# Benchtop_Power_Supply-v13.net
KiCad netlist of a schematic drawn in EAGLE
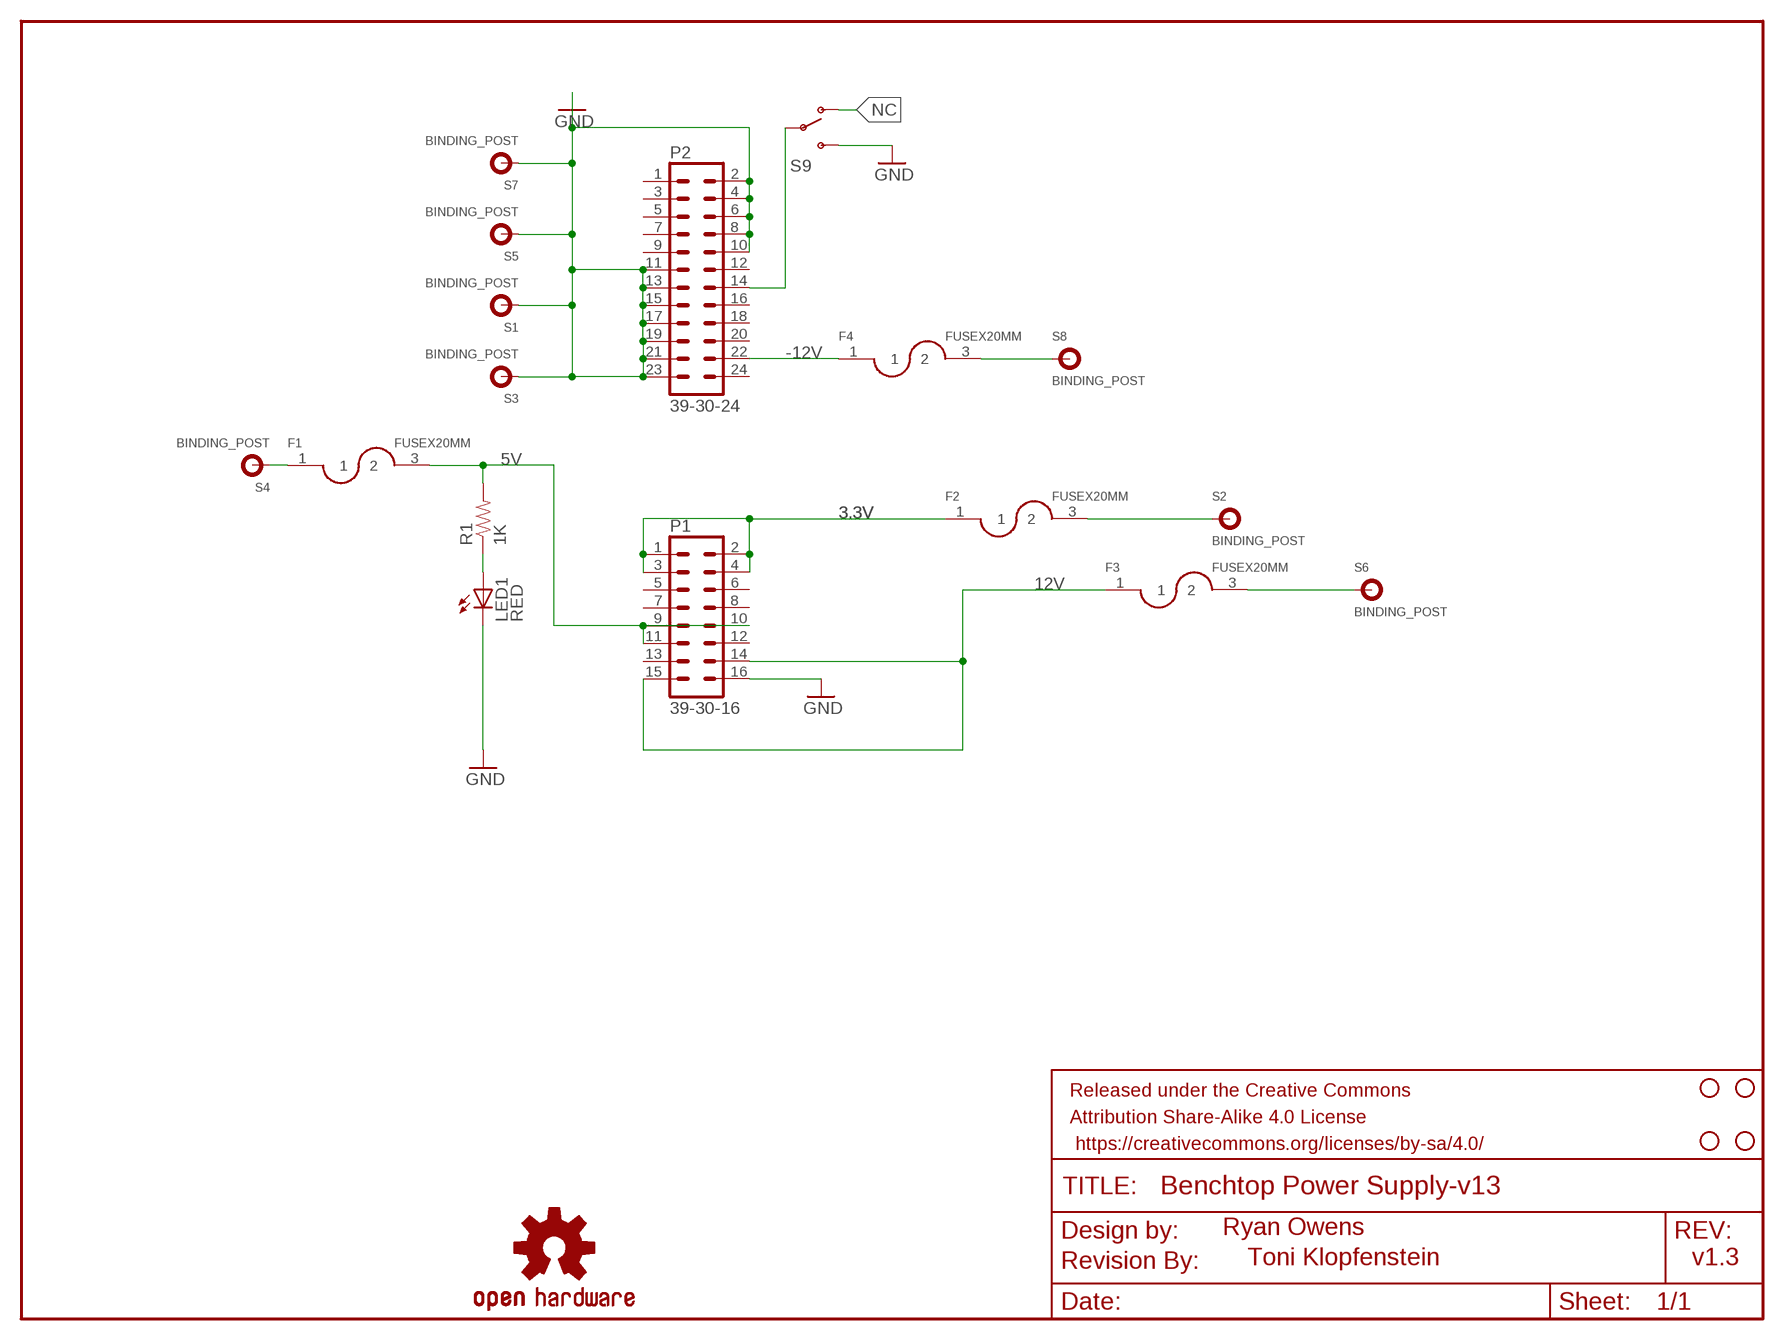
[diagram p0: schematic, sheet 1]

(export (version "E")
  (design (tool "Eeschema 10.0.6"))
  (components
    (comp (ref "F1")
      (value "FUSEX20MM")
      (footprint "eagle-import:FUSE_5MM")
      (libsource (lib "eagle-import") (part "FUSEX20MM"))
    )
    (comp (ref "F2")
      (value "FUSEX20MM")
      (footprint "eagle-import:FUSE_5MM")
      (libsource (lib "eagle-import") (part "FUSEX20MM"))
    )
    (comp (ref "F3")
      (value "FUSEX20MM")
      (footprint "eagle-import:FUSE_5MM")
      (libsource (lib "eagle-import") (part "FUSEX20MM"))
    )
    (comp (ref "F4")
      (value "FUSEX20MM")
      (footprint "eagle-import:FUSE_5MM")
      (libsource (lib "eagle-import") (part "FUSEX20MM"))
    )
    (comp (ref "FRAME1")
      (value "FRAME-LETTER")
      (footprint "eagle-import:CREATIVE_COMMONS")
      (libsource (lib "eagle-import") (part "FRAME-LETTER"))
    )
    (comp (ref "JP2")
      (value "STAND-OFF")
      (footprint "eagle-import:STAND-OFF")
      (libsource (lib "eagle-import") (part "STAND-OFF"))
    )
    (comp (ref "JP3")
      (value "STAND-OFF")
      (footprint "eagle-import:STAND-OFF")
      (libsource (lib "eagle-import") (part "STAND-OFF"))
    )
    (comp (ref "JP4")
      (value "STAND-OFF")
      (footprint "eagle-import:STAND-OFF")
      (libsource (lib "eagle-import") (part "STAND-OFF"))
    )
    (comp (ref "JP5")
      (value "STAND-OFF")
      (footprint "eagle-import:STAND-OFF")
      (libsource (lib "eagle-import") (part "STAND-OFF"))
    )
    (comp (ref "LED1")
      (value "RED")
      (footprint "eagle-import:LED5MM")
      (libsource (lib "eagle-import") (part "LED5MM"))
    )
    (comp (ref "LOGO1")
      (value "OSHW-LOGOL")
      (footprint "eagle-import:OSHW-LOGO-L")
      (libsource (lib "eagle-import") (part "OSHW-LOGOL"))
    )
    (comp (ref "P1")
      (value "39-30-16")
      (footprint "eagle-import:39-30-_16_")
      (libsource (lib "eagle-import") (part "39-30-?16?"))
    )
    (comp (ref "P2")
      (value "39-30-24")
      (footprint "eagle-import:39-30-_24_")
      (libsource (lib "eagle-import") (part "39-30-?24?"))
    )
    (comp (ref "R1")
      (value "1K")
      (footprint "eagle-import:AXIAL-0.3")
      (libsource (lib "eagle-import") (part "RESISTORPTH1"))
    )
    (comp (ref "S1")
      (value "BINDING_POST")
      (footprint "eagle-import:BINDING_POST")
      (libsource (lib "eagle-import") (part "BINDING_POST"))
    )
    (comp (ref "S2")
      (value "BINDING_POST")
      (footprint "eagle-import:BINDING_POST")
      (libsource (lib "eagle-import") (part "BINDING_POST"))
    )
    (comp (ref "S3")
      (value "BINDING_POST")
      (footprint "eagle-import:BINDING_POST")
      (libsource (lib "eagle-import") (part "BINDING_POST"))
    )
    (comp (ref "S4")
      (value "BINDING_POST")
      (footprint "eagle-import:BINDING_POST")
      (libsource (lib "eagle-import") (part "BINDING_POST"))
    )
    (comp (ref "S5")
      (value "BINDING_POST")
      (footprint "eagle-import:BINDING_POST")
      (libsource (lib "eagle-import") (part "BINDING_POST"))
    )
    (comp (ref "S6")
      (value "BINDING_POST")
      (footprint "eagle-import:BINDING_POST")
      (libsource (lib "eagle-import") (part "BINDING_POST"))
    )
    (comp (ref "S7")
      (value "BINDING_POST")
      (footprint "eagle-import:BINDING_POST")
      (libsource (lib "eagle-import") (part "BINDING_POST"))
    )
    (comp (ref "S8")
      (value "BINDING_POST")
      (footprint "eagle-import:BINDING_POST")
      (libsource (lib "eagle-import") (part "BINDING_POST"))
    )
    (comp (ref "S9")
      (value "SWITCH-SPDTKIT")
      (footprint "eagle-import:SWITCH-SPDT_KIT")
      (libsource (lib "eagle-import") (part "SWITCH-SPDTKIT"))
    )
    (comp (ref "U$1")
      (value "REVISION")
      (footprint "eagle-import:REVISION")
      (libsource (lib "eagle-import") (part "REVISION"))
    )
  )
  (nets
    (net (code "1") (name "/-12V") (class "Default")
      (node (ref "F4") (pin "1") (pinfunction "1_1") (pintype "bidirectional"))
      (node (ref "P2") (pin "22") (pinfunction "22_22") (pintype "passive"))
    )
    (net (code "2") (name "/3.3V") (class "Default")
      (node (ref "F2") (pin "1") (pinfunction "1_1") (pintype "bidirectional"))
      (node (ref "P1") (pin "1") (pinfunction "1_1") (pintype "passive"))
      (node (ref "P1") (pin "2") (pinfunction "2_2") (pintype "passive"))
      (node (ref "P1") (pin "3") (pinfunction "3_3") (pintype "passive"))
      (node (ref "P1") (pin "4") (pinfunction "4_4") (pintype "passive"))
    )
    (net (code "3") (name "/5V") (class "Default")
      (node (ref "F1") (pin "3") (pinfunction "2_3") (pintype "bidirectional"))
      (node (ref "P1") (pin "10") (pinfunction "10_10") (pintype "passive"))
      (node (ref "P1") (pin "11") (pinfunction "11_11") (pintype "passive"))
      (node (ref "P1") (pin "9") (pinfunction "9_9") (pintype "passive"))
      (node (ref "R1") (pin "P$2") (pinfunction "2_P$2") (pintype "passive"))
    )
    (net (code "4") (name "/12V") (class "Default")
      (node (ref "F3") (pin "1") (pinfunction "1_1") (pintype "bidirectional"))
      (node (ref "P1") (pin "14") (pinfunction "14_14") (pintype "passive"))
      (node (ref "P1") (pin "15") (pinfunction "15_15") (pintype "passive"))
    )
    (net (code "5") (name "GND") (class "Default")
      (node (ref "LED1") (pin "K") (pinfunction "C_K") (pintype "passive"))
      (node (ref "P1") (pin "16") (pinfunction "16_16") (pintype "passive"))
      (node (ref "P2") (pin "10") (pinfunction "10_10") (pintype "passive"))
      (node (ref "P2") (pin "11") (pinfunction "11_11") (pintype "passive"))
      (node (ref "P2") (pin "13") (pinfunction "13_13") (pintype "passive"))
      (node (ref "P2") (pin "15") (pinfunction "15_15") (pintype "passive"))
      (node (ref "P2") (pin "17") (pinfunction "17_17") (pintype "passive"))
      (node (ref "P2") (pin "19") (pinfunction "19_19") (pintype "passive"))
      (node (ref "P2") (pin "2") (pinfunction "2_2") (pintype "passive"))
      (node (ref "P2") (pin "21") (pinfunction "21_21") (pintype "passive"))
      (node (ref "P2") (pin "23") (pinfunction "23_23") (pintype "passive"))
      (node (ref "P2") (pin "4") (pinfunction "4_4") (pintype "passive"))
      (node (ref "P2") (pin "6") (pinfunction "6_6") (pintype "passive"))
      (node (ref "P2") (pin "8") (pinfunction "8_8") (pintype "passive"))
      (node (ref "S1") (pin "P$1") (pinfunction "P$1_P$1") (pintype "bidirectional"))
      (node (ref "S3") (pin "P$1") (pinfunction "P$1_P$1") (pintype "bidirectional"))
      (node (ref "S5") (pin "P$1") (pinfunction "P$1_P$1") (pintype "bidirectional"))
      (node (ref "S7") (pin "P$1") (pinfunction "P$1_P$1") (pintype "bidirectional"))
      (node (ref "S9") (pin "3") (pinfunction "S_3") (pintype "passive"))
    )
    (net (code "6") (name "NC") (class "Default")
      (node (ref "S9") (pin "1") (pinfunction "O_1") (pintype "passive"))
    )
    (net (code "7") (name "Net-(F1-Pad1)") (class "Default")
      (node (ref "F1") (pin "1") (pinfunction "1_1") (pintype "bidirectional"))
      (node (ref "S4") (pin "P$1") (pinfunction "P$1_P$1") (pintype "bidirectional"))
    )
    (net (code "8") (name "Net-(F2-2)") (class "Default")
      (node (ref "F2") (pin "3") (pinfunction "2_3") (pintype "bidirectional"))
      (node (ref "S2") (pin "P$1") (pinfunction "P$1_P$1") (pintype "bidirectional"))
    )
    (net (code "9") (name "Net-(F3-2)") (class "Default")
      (node (ref "F3") (pin "3") (pinfunction "2_3") (pintype "bidirectional"))
      (node (ref "S6") (pin "P$1") (pinfunction "P$1_P$1") (pintype "bidirectional"))
    )
    (net (code "10") (name "Net-(F4-2)") (class "Default")
      (node (ref "F4") (pin "3") (pinfunction "2_3") (pintype "bidirectional"))
      (node (ref "S8") (pin "P$1") (pinfunction "P$1_P$1") (pintype "bidirectional"))
    )
    (net (code "11") (name "Net-(R1-1)") (class "Default")
      (node (ref "LED1") (pin "A") (pinfunction "A_A") (pintype "passive"))
      (node (ref "R1") (pin "P$1") (pinfunction "1_P$1") (pintype "passive"))
    )
    (net (code "12") (name "Net-(S9-P)") (class "Default")
      (node (ref "P2") (pin "14") (pinfunction "14_14") (pintype "passive"))
      (node (ref "S9") (pin "2") (pinfunction "P_2") (pintype "passive"))
    )
    (net (code "13") (name "unconnected-(P1-Pad5)") (class "Default")
      (node (ref "P1") (pin "5") (pinfunction "5_5") (pintype "passive"))
    )
    (net (code "14") (name "unconnected-(P1-Pad6)") (class "Default")
      (node (ref "P1") (pin "6") (pinfunction "6_6") (pintype "passive"))
    )
    (net (code "15") (name "unconnected-(P1-Pad7)") (class "Default")
      (node (ref "P1") (pin "7") (pinfunction "7_7") (pintype "passive"))
    )
    (net (code "16") (name "unconnected-(P1-Pad8)") (class "Default")
      (node (ref "P1") (pin "8") (pinfunction "8_8") (pintype "passive"))
    )
    (net (code "17") (name "unconnected-(P1-Pad12)") (class "Default")
      (node (ref "P1") (pin "12") (pinfunction "12_12") (pintype "passive"))
    )
    (net (code "18") (name "unconnected-(P1-Pad13)") (class "Default")
      (node (ref "P1") (pin "13") (pinfunction "13_13") (pintype "passive"))
    )
    (net (code "19") (name "unconnected-(P2-Pad1)") (class "Default")
      (node (ref "P2") (pin "1") (pinfunction "1_1") (pintype "passive"))
    )
    (net (code "20") (name "unconnected-(P2-Pad3)") (class "Default")
      (node (ref "P2") (pin "3") (pinfunction "3_3") (pintype "passive"))
    )
    (net (code "21") (name "unconnected-(P2-Pad5)") (class "Default")
      (node (ref "P2") (pin "5") (pinfunction "5_5") (pintype "passive"))
    )
    (net (code "22") (name "unconnected-(P2-Pad7)") (class "Default")
      (node (ref "P2") (pin "7") (pinfunction "7_7") (pintype "passive"))
    )
    (net (code "23") (name "unconnected-(P2-Pad9)") (class "Default")
      (node (ref "P2") (pin "9") (pinfunction "9_9") (pintype "passive"))
    )
    (net (code "24") (name "unconnected-(P2-Pad12)") (class "Default")
      (node (ref "P2") (pin "12") (pinfunction "12_12") (pintype "passive"))
    )
    (net (code "25") (name "unconnected-(P2-Pad16)") (class "Default")
      (node (ref "P2") (pin "16") (pinfunction "16_16") (pintype "passive"))
    )
    (net (code "26") (name "unconnected-(P2-Pad18)") (class "Default")
      (node (ref "P2") (pin "18") (pinfunction "18_18") (pintype "passive"))
    )
    (net (code "27") (name "unconnected-(P2-Pad20)") (class "Default")
      (node (ref "P2") (pin "20") (pinfunction "20_20") (pintype "passive"))
    )
    (net (code "28") (name "unconnected-(P2-Pad24)") (class "Default")
      (node (ref "P2") (pin "24") (pinfunction "24_24") (pintype "passive"))
    )
  )
)
